# UBT.net
KiCad netlist of a schematic drawn in Altium Designer
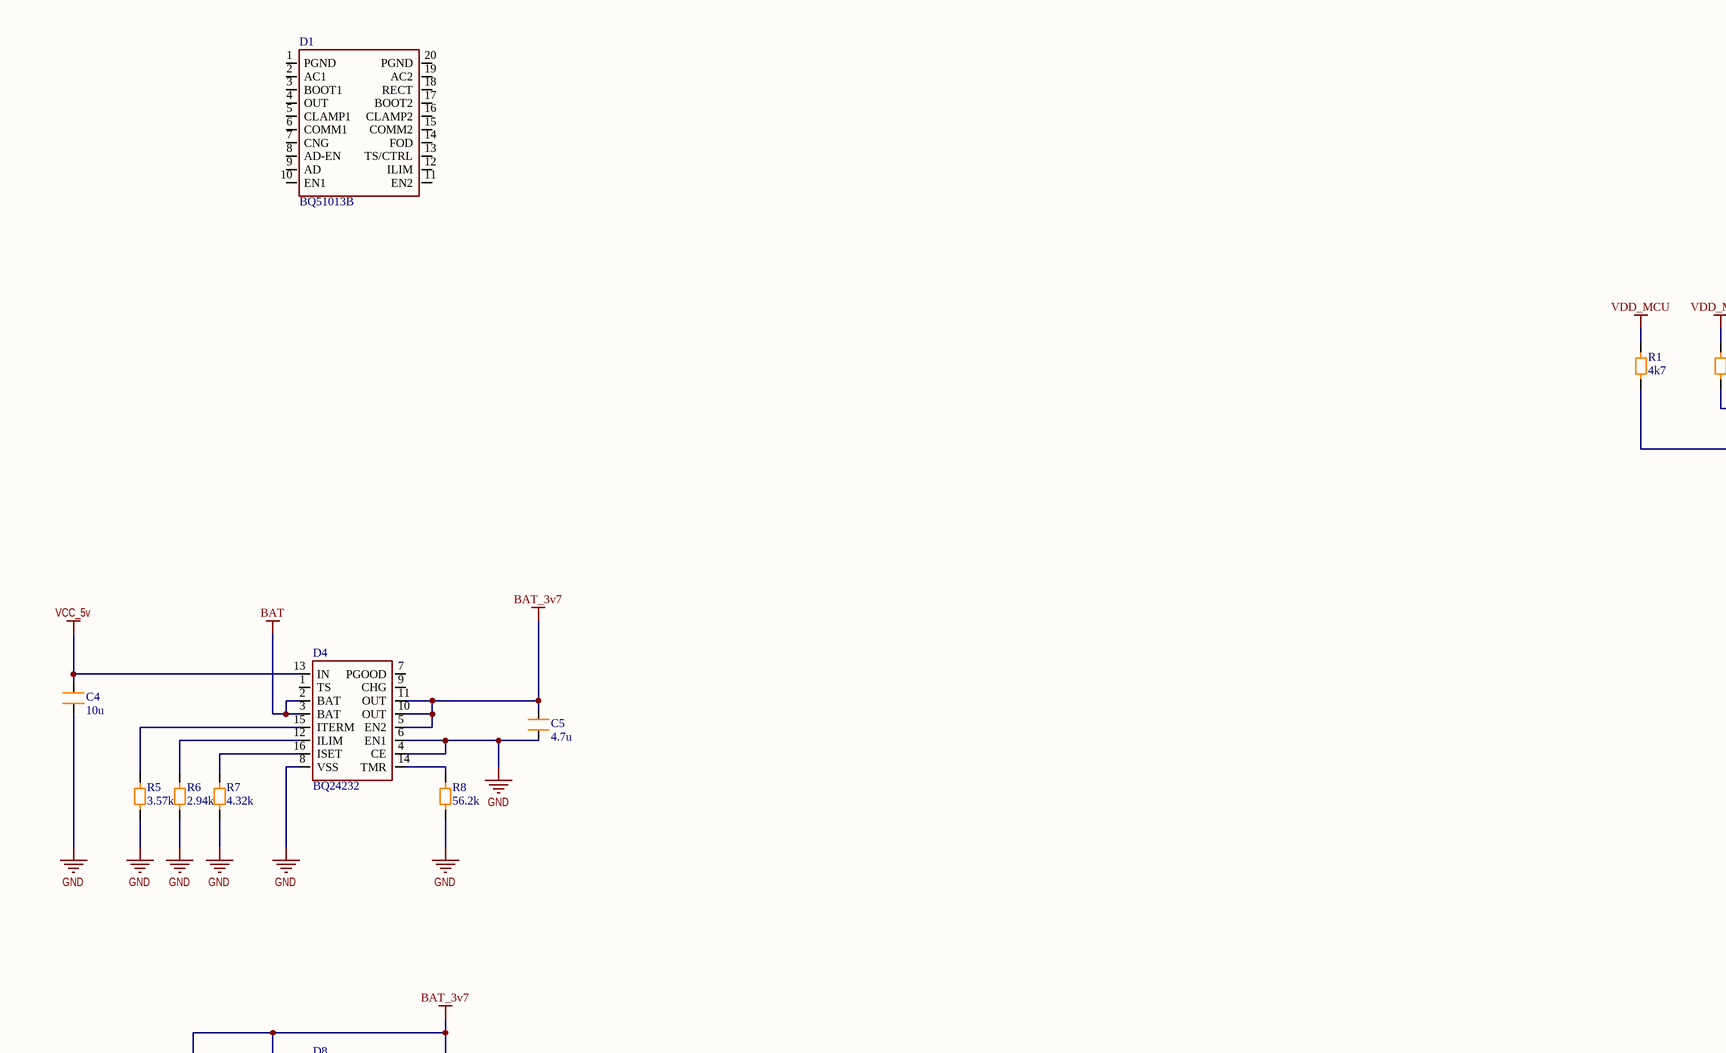
[diagram p0: UBT.SchDoc, top left]
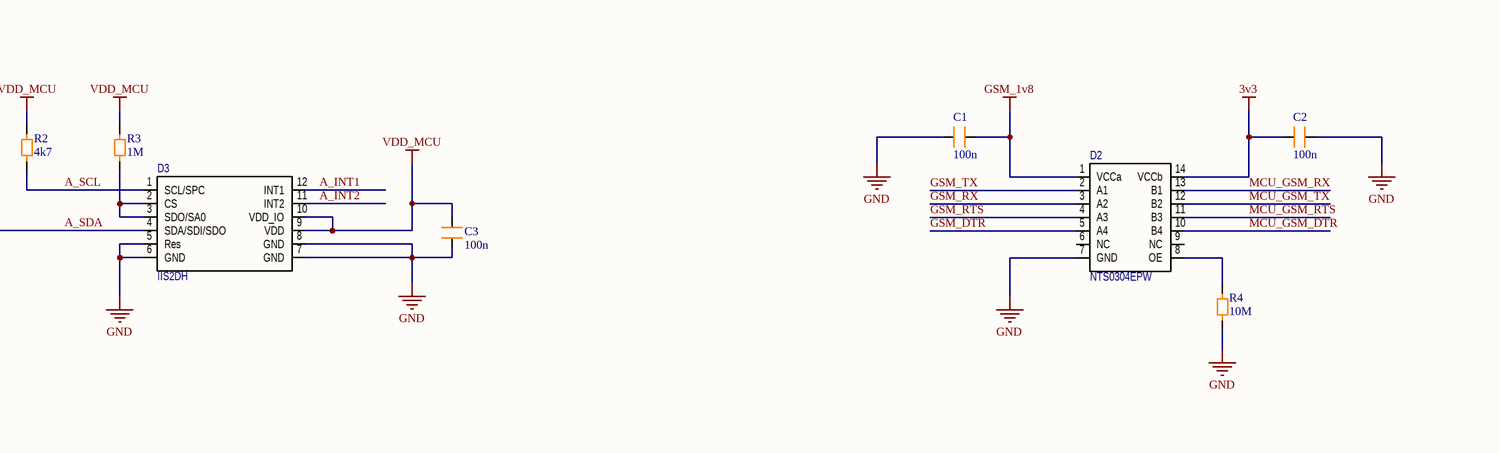
[diagram p1: UBT.SchDoc, top right]
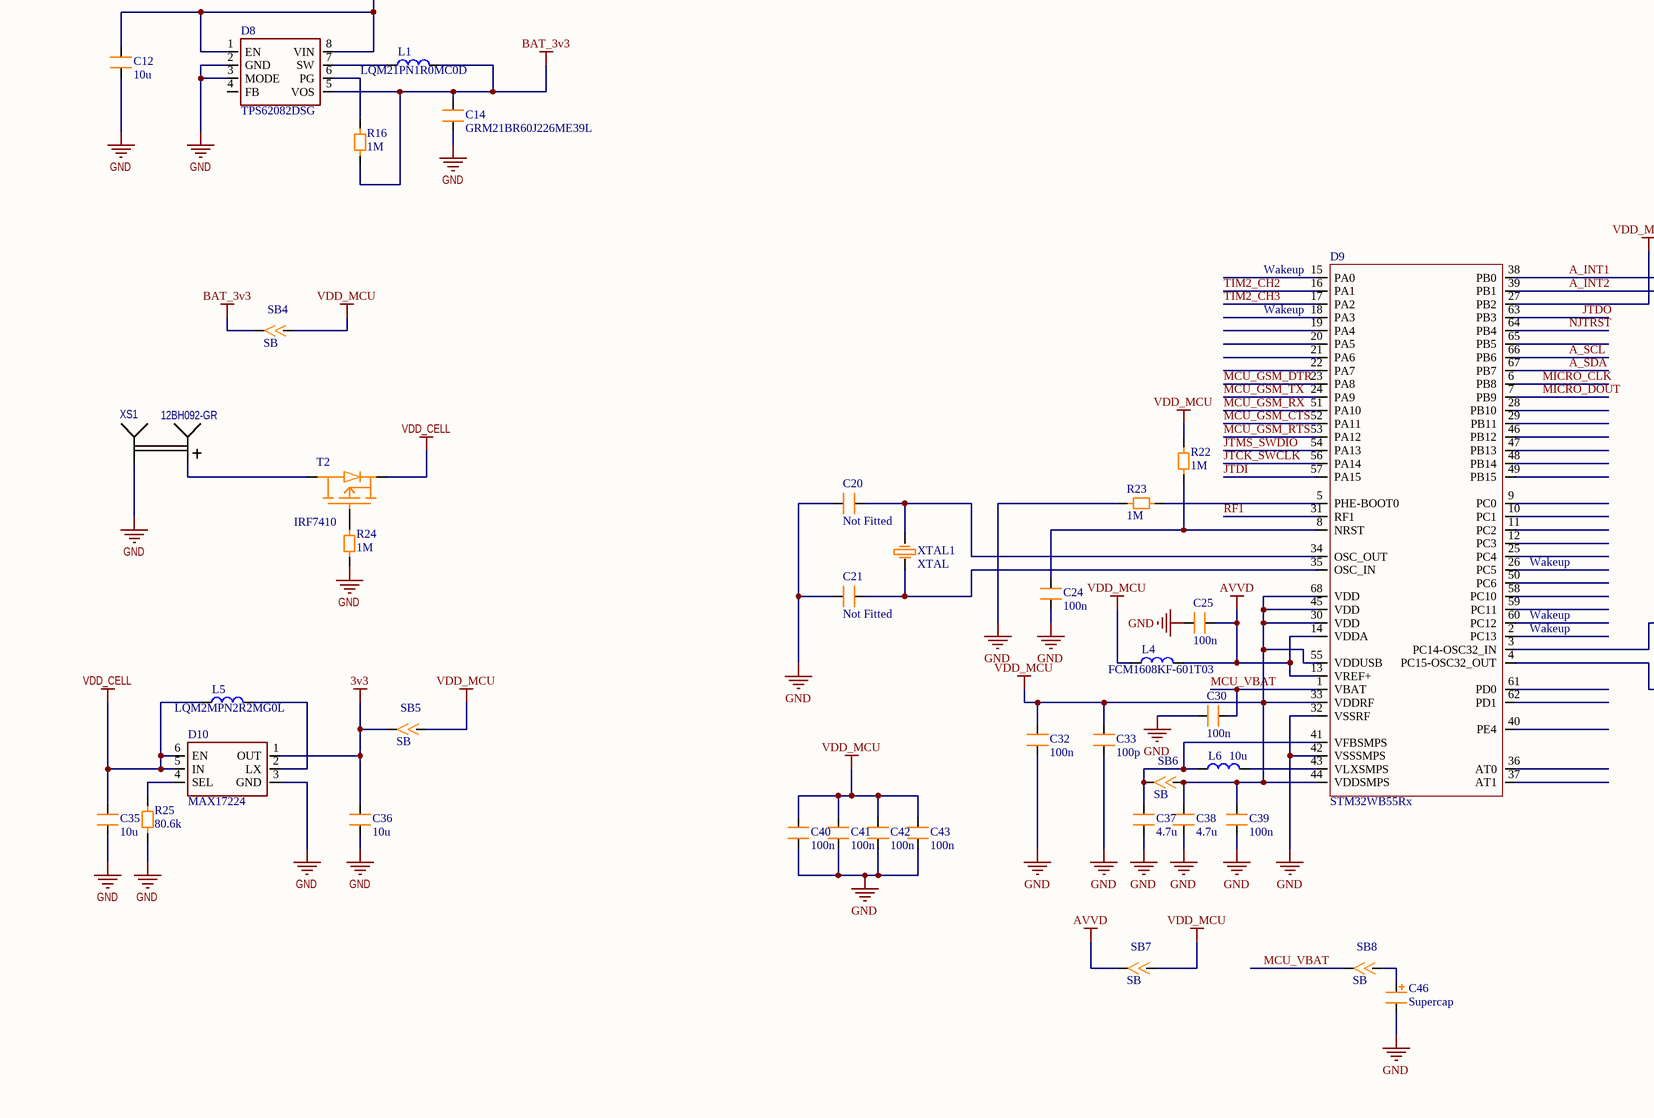
[diagram p2: UBT.SchDoc, bottom left]
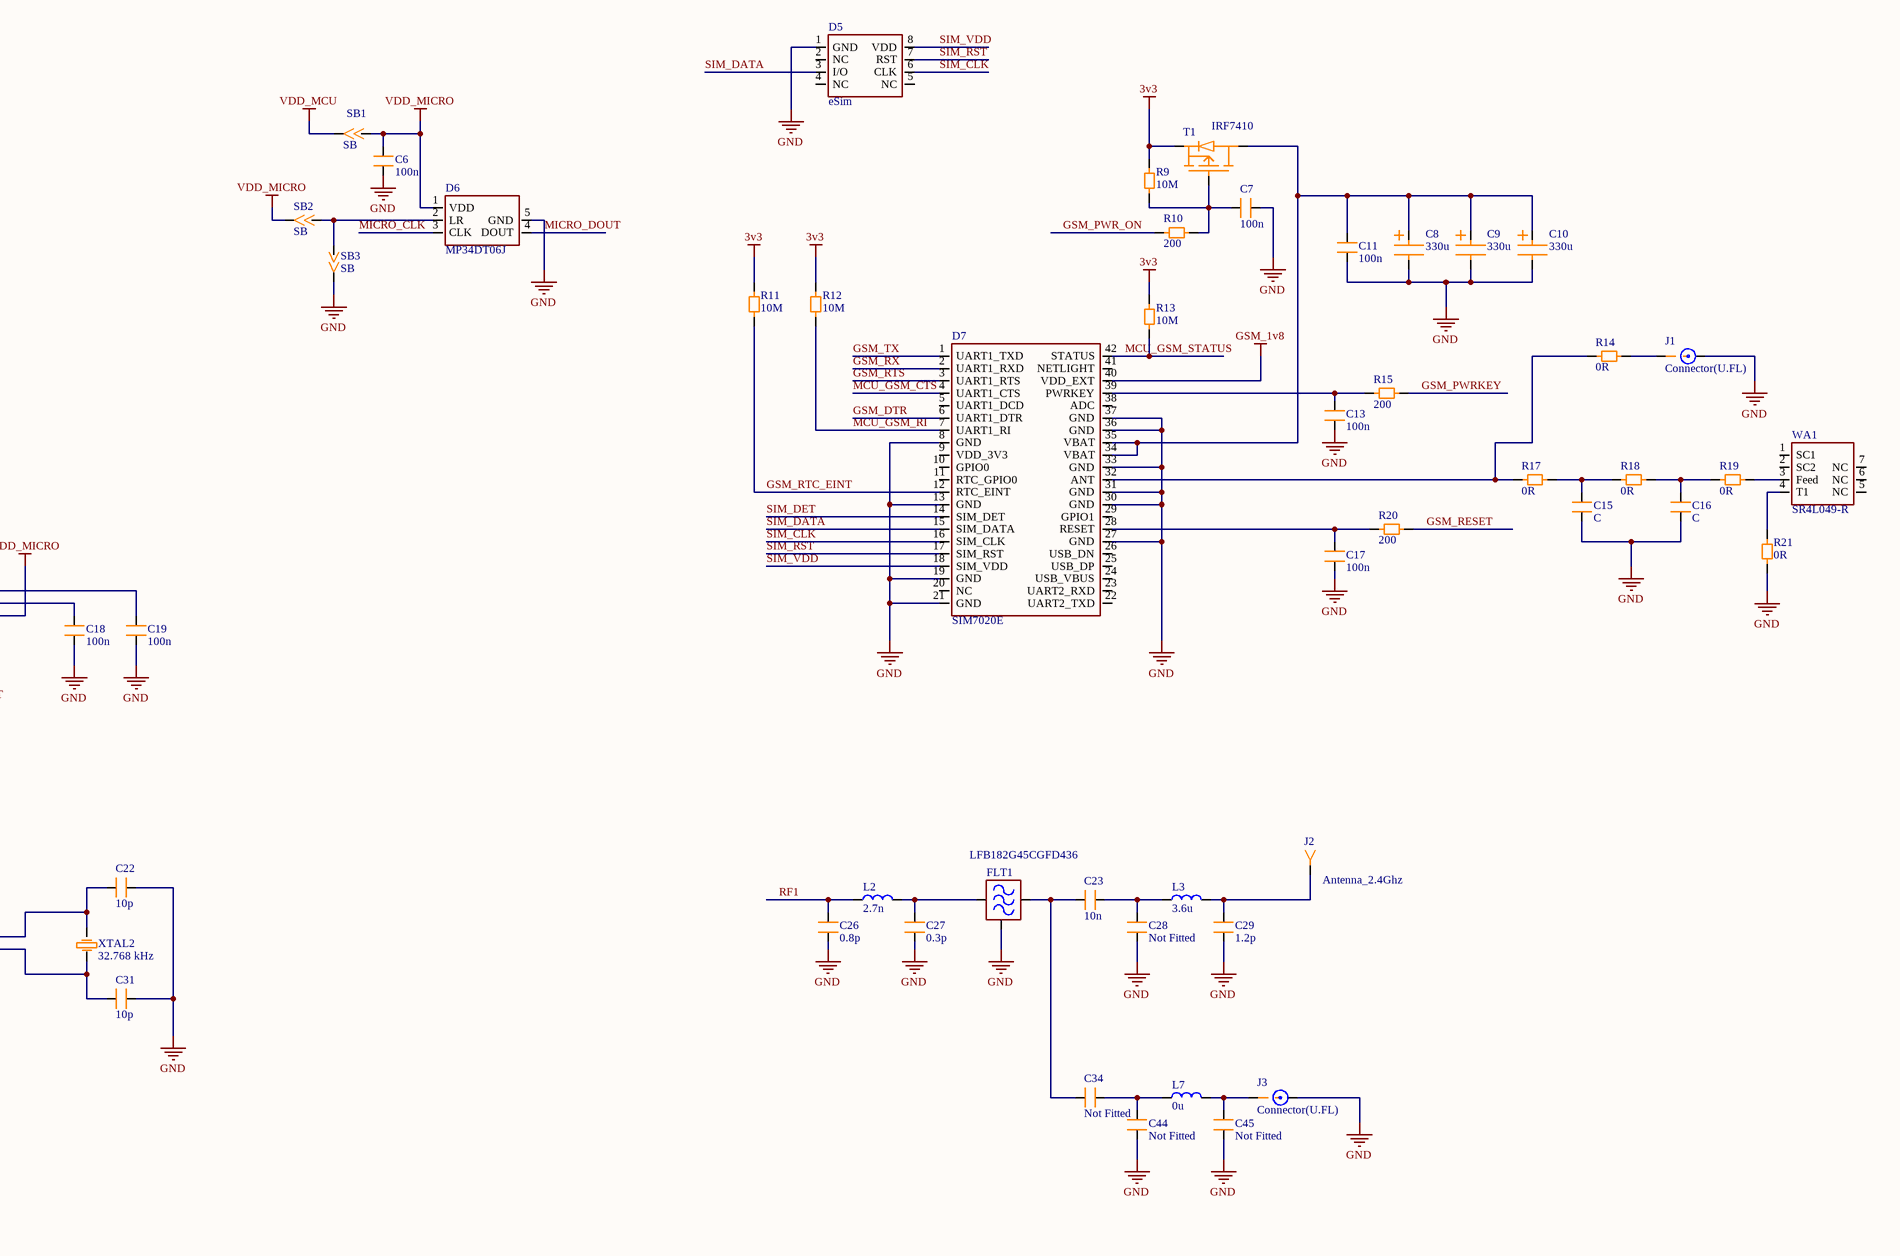
[diagram p3: UBT.SchDoc, bottom right]

(export (version "E")
  (design (tool "Eeschema 10.0.6"))
  (components
    (comp (ref "C1") (value "100n") (footprint "C0402") (libsource (lib "Schlib1") (part "C")))
    (comp (ref "C2") (value "100n") (footprint "C0402") (libsource (lib "Schlib1") (part "C")))
    (comp (ref "C3") (value "100n") (footprint "C0402") (libsource (lib "Schlib1") (part "C")))
    (comp (ref "C4") (value "10u") (footprint "C0603") (libsource (lib "Schlib1") (part "C")))
    (comp (ref "C5") (value "4.7u") (footprint "C0603") (libsource (lib "Schlib1") (part "C")))
    (comp (ref "C6") (value "100n") (footprint "C0402") (libsource (lib "Schlib1") (part "C")))
    (comp (ref "C7") (value "100n") (footprint "C0402") (libsource (lib "Schlib1") (part "C")))
    (comp (ref "C8") (value "330u") (footprint "C_TYPE_D") (libsource (lib "Schlib1") (part "C_TANTAL")))
    (comp (ref "C9") (value "330u") (footprint "C_TYPE_D") (libsource (lib "Schlib1") (part "C_TANTAL")))
    (comp (ref "C10") (value "330u") (footprint "C_TYPE_D") (libsource (lib "Schlib1") (part "C_TANTAL")))
    (comp (ref "C11") (value "100n") (footprint "C0402") (libsource (lib "Schlib1") (part "C")))
    (comp (ref "C12") (value "10u") (footprint "C0603") (libsource (lib "Schlib1") (part "C")))
    (comp (ref "C13") (value "100n") (footprint "C0402") (libsource (lib "Schlib1") (part "C")))
    (comp (ref "C14") (value "GRM21BR60J226ME39L") (footprint "C0805") (libsource (lib "Schlib1") (part "C")))
    (comp (ref "C15") (value "C") (footprint "C0402") (libsource (lib "Schlib1") (part "C")))
    (comp (ref "C16") (value "C") (footprint "C0402") (libsource (lib "Schlib1") (part "C")))
    (comp (ref "C17") (value "100n") (footprint "C0402") (libsource (lib "Schlib1") (part "C")))
    (comp (ref "C18") (value "100n") (footprint "C0402") (libsource (lib "Schlib1") (part "C")))
    (comp (ref "C19") (value "100n") (footprint "C0402") (libsource (lib "Schlib1") (part "C")))
    (comp (ref "C20") (value "Not Fitted") (footprint "C0402") (libsource (lib "Schlib1") (part "C")))
    (comp (ref "C21") (value "Not Fitted") (footprint "C0402") (libsource (lib "Schlib1") (part "C")))
    (comp (ref "C22") (value "10p") (footprint "C0402") (libsource (lib "Schlib1") (part "C")))
    (comp (ref "C23") (value "10n") (footprint "C0402") (libsource (lib "Schlib1") (part "C")))
    (comp (ref "C24") (value "100n") (footprint "C0402") (libsource (lib "Schlib1") (part "C")))
    (comp (ref "C25") (value "100n") (footprint "C0402") (libsource (lib "Schlib1") (part "C")))
    (comp (ref "C26") (value "0.8p") (footprint "C0402") (libsource (lib "Schlib1") (part "C")))
    (comp (ref "C27") (value "0.3p") (footprint "C0402") (libsource (lib "Schlib1") (part "C")))
    (comp (ref "C28") (value "Not Fitted") (footprint "C0402") (libsource (lib "Schlib1") (part "C")))
    (comp (ref "C29") (value "1.2p") (footprint "C0402") (libsource (lib "Schlib1") (part "C")))
    (comp (ref "C30") (value "100n") (footprint "C0402") (libsource (lib "Schlib1") (part "C")))
    (comp (ref "C31") (value "10p") (footprint "C0402") (libsource (lib "Schlib1") (part "C")))
    (comp (ref "C32") (value "100n") (footprint "C0402") (libsource (lib "Schlib1") (part "C")))
    (comp (ref "C33") (value "100p") (footprint "C0402") (libsource (lib "Schlib1") (part "C")))
    (comp (ref "C34") (value "Not Fitted") (footprint "C0402") (libsource (lib "Schlib1") (part "C")))
    (comp (ref "C35") (value "10u") (footprint "C0603") (libsource (lib "Schlib1") (part "C")))
    (comp (ref "C36") (value "10u") (footprint "C0603") (libsource (lib "Schlib1") (part "C")))
    (comp (ref "C37") (value "4.7u") (footprint "C0402") (libsource (lib "Schlib1") (part "C")))
    (comp (ref "C38") (value "4.7u") (footprint "C0402") (libsource (lib "Schlib1") (part "C")))
    (comp (ref "C39") (value "100n") (footprint "C0402") (libsource (lib "Schlib1") (part "C")))
    (comp (ref "C40") (value "100n") (footprint "C0402") (libsource (lib "Schlib1") (part "C")))
    (comp (ref "C41") (value "100n") (footprint "C0402") (libsource (lib "Schlib1") (part "C")))
    (comp (ref "C42") (value "100n") (footprint "C0402") (libsource (lib "Schlib1") (part "C")))
    (comp (ref "C43") (value "100n") (footprint "C0402") (libsource (lib "Schlib1") (part "C")))
    (comp (ref "C44") (value "Not Fitted") (footprint "C0402") (libsource (lib "Schlib1") (part "C")))
    (comp (ref "C45") (value "Not Fitted") (footprint "C0402") (libsource (lib "Schlib1") (part "C")))
    (comp (ref "C46")
      (value "Supercap")
      (footprint "Supercap_5mm")
      (libsource (lib "Schlib1") (part "Supercap"))
    )
    (comp (ref "D1") (value "BQ51013B") (footprint "VQFN20") (libsource (lib "Schlib1") (part "BQ51013B")))
    (comp (ref "D2")
      (value "NTS0304EPW")
      (footprint "TSSOP14")
      (libsource (lib "Schlib1") (part "NTS0304EPW"))
    )
    (comp (ref "D3") (value "IIS2DH") (footprint "LGA12") (libsource (lib "Schlib1") (part "IIS2DH")))
    (comp (ref "D4") (value "BQ24232") (footprint "VQFN-16") (libsource (lib "Schlib1") (part "BQ24232")))
    (comp (ref "D5") (value "eSim") (footprint "VQFN8") (libsource (lib "Schlib1") (part "eSim")))
    (comp (ref "D6")
      (value "MP34DT06J")
      (footprint "MP34DT06J")
      (libsource (lib "Schlib1") (part "MP34DT06J"))
    )
    (comp (ref "D7") (value "SIM7020E") (footprint "SIM7020E") (libsource (lib "Schlib1") (part "SIM7020E")))
    (comp (ref "D8") (value "TPS62082DSG") (footprint "WSON8") (libsource (lib "Schlib1") (part "TPS62081")))
    (comp (ref "D9")
      (value "STM32WB55Rx")
      (footprint "VFQFPN68")
      (libsource (lib "Schlib1") (part "STM32WB55Rx"))
    )
    (comp (ref "D10") (value "MAX17224") (libsource (lib "Schlib1") (part "MAX17224")))
    (comp (ref "FLT1")
      (value "LFB182G45CGFD436")
      (footprint "LFB182G45CGFD436")
      (libsource (lib "Schlib1") (part "LFB182G45CGFD436"))
    )
    (comp (ref "J1")
      (value "Connector(U.FL)")
      (footprint "U.FL")
      (libsource (lib "Schlib1") (part "Connector(U.FL)"))
    )
    (comp (ref "J2")
      (value "Antenna_2.4Ghz")
      (footprint "Antenna_2.4Ghz")
      (libsource (lib "Schlib1") (part "Antenna_2.4Ghz"))
    )
    (comp (ref "J3")
      (value "Connector(U.FL)")
      (footprint "U.FL")
      (libsource (lib "Schlib1") (part "Connector(U.FL)"))
    )
    (comp (ref "L1") (value "LQM21PN1R0MC0D") (footprint "L0805") (libsource (lib "Schlib1") (part "L")))
    (comp (ref "L2") (value "2.7n") (footprint "L0402") (libsource (lib "Schlib1") (part "L")))
    (comp (ref "L3") (value "3.6u") (footprint "L0402") (libsource (lib "Schlib1") (part "L")))
    (comp (ref "L4") (value "FCM1608KF-601T03") (footprint "L1608") (libsource (lib "Schlib1") (part "L")))
    (comp (ref "L5") (value "LQM2MPN2R2MG0L") (footprint "L2016") (libsource (lib "Schlib1") (part "L")))
    (comp (ref "L6") (value "10u") (footprint "L0805") (libsource (lib "Schlib1") (part "L")))
    (comp (ref "L7") (value "0u") (footprint "L0402") (libsource (lib "Schlib1") (part "L")))
    (comp (ref "R1") (value "4k7") (footprint "R0402") (libsource (lib "Schlib1") (part "R")))
    (comp (ref "R2") (value "4k7") (footprint "R0402") (libsource (lib "Schlib1") (part "R")))
    (comp (ref "R3") (value "1M") (footprint "R0402") (libsource (lib "Schlib1") (part "R")))
    (comp (ref "R4") (value "10M") (footprint "R0402") (libsource (lib "Schlib1") (part "R")))
    (comp (ref "R5") (value "3.57k") (footprint "R0402") (libsource (lib "Schlib1") (part "R")))
    (comp (ref "R6") (value "2.94k") (footprint "R0402") (libsource (lib "Schlib1") (part "R")))
    (comp (ref "R7") (value "4.32k") (footprint "R0402") (libsource (lib "Schlib1") (part "R")))
    (comp (ref "R8") (value "56.2k") (footprint "R0402") (libsource (lib "Schlib1") (part "R")))
    (comp (ref "R9") (value "10M") (footprint "R0402") (libsource (lib "Schlib1") (part "R")))
    (comp (ref "R10") (value "200") (footprint "R0402") (libsource (lib "Schlib1") (part "R")))
    (comp (ref "R11") (value "10M") (footprint "R0402") (libsource (lib "Schlib1") (part "R")))
    (comp (ref "R12") (value "10M") (footprint "R0402") (libsource (lib "Schlib1") (part "R")))
    (comp (ref "R13") (value "10M") (footprint "R0402") (libsource (lib "Schlib1") (part "R")))
    (comp (ref "R14") (value "0R") (footprint "R0402") (libsource (lib "Schlib1") (part "R")))
    (comp (ref "R15") (value "200") (footprint "R0402") (libsource (lib "Schlib1") (part "R")))
    (comp (ref "R16") (value "1M") (footprint "R0402") (libsource (lib "Schlib1") (part "R")))
    (comp (ref "R17") (value "0R") (footprint "R0402") (libsource (lib "Schlib1") (part "R")))
    (comp (ref "R18") (value "0R") (footprint "R0402") (libsource (lib "Schlib1") (part "R")))
    (comp (ref "R19") (value "0R") (footprint "R0402") (libsource (lib "Schlib1") (part "R")))
    (comp (ref "R20") (value "200") (footprint "R0402") (libsource (lib "Schlib1") (part "R")))
    (comp (ref "R21") (value "0R") (footprint "R0402") (libsource (lib "Schlib1") (part "R")))
    (comp (ref "R22") (value "1M") (footprint "R0402") (libsource (lib "Schlib1") (part "R")))
    (comp (ref "R23") (value "1M") (footprint "R0402") (libsource (lib "Schlib1") (part "R")))
    (comp (ref "R24") (value "1M") (footprint "R0402") (libsource (lib "Schlib1") (part "R")))
    (comp (ref "R25") (value "80.6k") (footprint "R0402") (libsource (lib "Schlib1") (part "R")))
    (comp (ref "SB1") (value "SB") (footprint "SB") (libsource (lib "Schlib1") (part "SB")))
    (comp (ref "SB2") (value "SB") (footprint "SB") (libsource (lib "Schlib1") (part "SB")))
    (comp (ref "SB3") (value "SB") (footprint "SB") (libsource (lib "Schlib1") (part "SB")))
    (comp (ref "SB4") (value "SB") (footprint "SB") (libsource (lib "Schlib1") (part "SB")))
    (comp (ref "SB5") (value "SB") (footprint "SB") (libsource (lib "Schlib1") (part "SB")))
    (comp (ref "SB6") (value "SB") (footprint "SB") (libsource (lib "Schlib1") (part "SB")))
    (comp (ref "SB7") (value "SB") (footprint "SB") (libsource (lib "Schlib1") (part "SB")))
    (comp (ref "SB8") (value "SB") (footprint "SB") (libsource (lib "Schlib1") (part "SB")))
    (comp (ref "T1") (value "IRF7410") (footprint "SO8") (libsource (lib "Schlib1") (part "IRF7410")))
    (comp (ref "T2") (value "IRF7410") (footprint "SO8") (libsource (lib "Schlib1") (part "IRF7410")))
    (comp (ref "WA1")
      (value "SR4L049-R")
      (footprint "SR4L049-R")
      (libsource (lib "Schlib1") (part "SR4L049-R"))
    )
    (comp (ref "XS1")
      (value "12BH092-GR")
      (footprint "12BH092-GR")
      (libsource (lib "Schlib1") (part "12BH092-GR"))
    )
    (comp (ref "XTAL1") (value "XTAL") (footprint "NX2016SA") (libsource (lib "Schlib1") (part "XTAL")))
    (comp (ref "XTAL2")
      (value "32.768 kHz")
      (footprint "NX2012SA")
      (libsource (lib "Schlib1") (part "32.768 kHz"))
    )
  )
  (nets
    (net (code "1") (name "/A_INT1") (class "Default")
      (node (ref "C19") (pin "2") (pinfunction "2_2") (pintype "passive"))
      (node (ref "D3") (pin "12") (pinfunction "INT1_12") (pintype "passive"))
      (node (ref "D9") (pin "38") (pinfunction "PB0_38") (pintype "passive"))
    )
    (net (code "2") (name "/A_INT2") (class "Default")
      (node (ref "C18") (pin "2") (pinfunction "2_2") (pintype "passive"))
      (node (ref "D3") (pin "11") (pinfunction "INT2_11") (pintype "passive"))
      (node (ref "D9") (pin "39") (pinfunction "PB1_39") (pintype "passive"))
    )
    (net (code "3") (name "/A_SCL") (class "Default")
      (node (ref "D3") (pin "1") (pinfunction "SCL/SPC_1") (pintype "passive"))
      (node (ref "D9") (pin "66") (pinfunction "PB6_66") (pintype "passive"))
      (node (ref "R2") (pin "1") (pinfunction "1_1") (pintype "passive"))
    )
    (net (code "4") (name "/A_SDA") (class "Default")
      (node (ref "D3") (pin "4") (pinfunction "SDA/SDI/SDO_4") (pintype "passive"))
      (node (ref "D9") (pin "67") (pinfunction "PB7_67") (pintype "passive"))
      (node (ref "R1") (pin "1") (pinfunction "1_1") (pintype "passive"))
    )
    (net (code "5") (name "/GSM_DTR") (class "Default")
      (node (ref "D2") (pin "5") (pinfunction "A4_5") (pintype "passive"))
      (node (ref "D7") (pin "6") (pinfunction "UART1_DTR_6") (pintype "passive"))
    )
    (net (code "6") (name "/GSM_PWRKEY") (class "Default")
      (node (ref "R15") (pin "2") (pinfunction "2_2") (pintype "passive"))
    )
    (net (code "7") (name "/GSM_PWR_ON") (class "Default")
      (node (ref "R10") (pin "1") (pinfunction "1_1") (pintype "passive"))
    )
    (net (code "8") (name "/GSM_RESET") (class "Default")
      (node (ref "R20") (pin "2") (pinfunction "2_2") (pintype "passive"))
    )
    (net (code "9") (name "/GSM_RTC_EINT") (class "Default")
      (node (ref "D7") (pin "12") (pinfunction "RTC_EINT_12") (pintype "passive"))
      (node (ref "R11") (pin "2") (pinfunction "2_2") (pintype "passive"))
    )
    (net (code "10") (name "/GSM_RTS") (class "Default")
      (node (ref "D2") (pin "4") (pinfunction "A3_4") (pintype "passive"))
      (node (ref "D7") (pin "3") (pinfunction "UART1_RTS_3") (pintype "passive"))
    )
    (net (code "11") (name "/GSM_RX") (class "Default")
      (node (ref "D2") (pin "3") (pinfunction "A2_3") (pintype "passive"))
      (node (ref "D7") (pin "2") (pinfunction "UART1_RXD_2") (pintype "passive"))
    )
    (net (code "12") (name "/GSM_TX") (class "Default")
      (node (ref "D2") (pin "2") (pinfunction "A1_2") (pintype "passive"))
      (node (ref "D7") (pin "1") (pinfunction "UART1_TXD_1") (pintype "passive"))
    )
    (net (code "13") (name "/JTCK_SWCLK") (class "Default")
      (node (ref "D9") (pin "56") (pinfunction "PA14_56") (pintype "passive"))
    )
    (net (code "14") (name "/JTDI") (class "Default")
      (node (ref "D9") (pin "57") (pinfunction "PA15_57") (pintype "passive"))
    )
    (net (code "15") (name "/JTDO") (class "Default")
      (node (ref "D9") (pin "63") (pinfunction "PB3_63") (pintype "passive"))
    )
    (net (code "16") (name "/JTMS_SWDIO") (class "Default")
      (node (ref "D9") (pin "54") (pinfunction "PA13_54") (pintype "passive"))
    )
    (net (code "17") (name "/MCU_GSM_CTS") (class "Default")
      (node (ref "D7") (pin "4") (pinfunction "UART1_CTS_4") (pintype "passive"))
      (node (ref "D9") (pin "52") (pinfunction "PA11_52") (pintype "passive"))
    )
    (net (code "18") (name "/MCU_GSM_DTR") (class "Default")
      (node (ref "D2") (pin "10") (pinfunction "B4_10") (pintype "passive"))
      (node (ref "D9") (pin "23") (pinfunction "PA8_23") (pintype "passive"))
    )
    (net (code "19") (name "/MCU_GSM_RI") (class "Default")
      (node (ref "D7") (pin "7") (pinfunction "UART1_RI_7") (pintype "passive"))
      (node (ref "R12") (pin "2") (pinfunction "2_2") (pintype "passive"))
    )
    (net (code "20") (name "/MCU_GSM_RTS") (class "Default")
      (node (ref "D2") (pin "11") (pinfunction "B3_11") (pintype "passive"))
      (node (ref "D9") (pin "53") (pinfunction "PA12_53") (pintype "passive"))
    )
    (net (code "21") (name "/MCU_GSM_RX") (class "Default")
      (node (ref "D2") (pin "13") (pinfunction "B1_13") (pintype "passive"))
      (node (ref "D9") (pin "51") (pinfunction "PA10_51") (pintype "passive"))
    )
    (net (code "22") (name "/MCU_GSM_STATUS") (class "Default")
      (node (ref "D7") (pin "42") (pinfunction "STATUS_42") (pintype "passive"))
      (node (ref "R13") (pin "2") (pinfunction "2_2") (pintype "passive"))
    )
    (net (code "23") (name "/MCU_GSM_TX") (class "Default")
      (node (ref "D2") (pin "12") (pinfunction "B2_12") (pintype "passive"))
      (node (ref "D9") (pin "24") (pinfunction "PA9_24") (pintype "passive"))
    )
    (net (code "24") (name "/MCU_VBAT") (class "Default")
      (node (ref "C30") (pin "1") (pinfunction "1_1") (pintype "passive"))
      (node (ref "D9") (pin "1") (pinfunction "VBAT_1") (pintype "passive"))
      (node (ref "SB8") (pin "1") (pinfunction "1_1") (pintype "passive"))
    )
    (net (code "25") (name "/MICRO_CLK") (class "Default")
      (node (ref "D6") (pin "3") (pinfunction "CLK_3") (pintype "passive"))
      (node (ref "D9") (pin "6") (pinfunction "PB8_6") (pintype "passive"))
    )
    (net (code "26") (name "/NJTRST") (class "Default")
      (node (ref "D9") (pin "64") (pinfunction "PB4_64") (pintype "passive"))
    )
    (net (code "27") (name "/RF1") (class "Default")
      (node (ref "C26") (pin "2") (pinfunction "2_2") (pintype "passive"))
      (node (ref "D9") (pin "31") (pinfunction "RF1_31") (pintype "passive"))
      (node (ref "L2") (pin "1") (pinfunction "1_1") (pintype "passive"))
    )
    (net (code "28") (name "/SIM_CLK") (class "Default")
      (node (ref "D5") (pin "6") (pinfunction "CLK_6") (pintype "passive"))
      (node (ref "D7") (pin "16") (pinfunction "SIM_CLK_16") (pintype "passive"))
    )
    (net (code "29") (name "/SIM_DATA") (class "Default")
      (node (ref "D5") (pin "3") (pinfunction "I/O_3") (pintype "passive"))
      (node (ref "D7") (pin "15") (pinfunction "SIM_DATA_15") (pintype "passive"))
    )
    (net (code "30") (name "/SIM_DET") (class "Default")
      (node (ref "D7") (pin "14") (pinfunction "SIM_DET_14") (pintype "passive"))
    )
    (net (code "31") (name "/SIM_RST") (class "Default")
      (node (ref "D5") (pin "7") (pinfunction "RST_7") (pintype "passive"))
      (node (ref "D7") (pin "17") (pinfunction "SIM_RST_17") (pintype "passive"))
    )
    (net (code "32") (name "/SIM_VDD") (class "Default")
      (node (ref "D5") (pin "8") (pinfunction "VDD_8") (pintype "passive"))
      (node (ref "D7") (pin "18") (pinfunction "SIM_VDD_18") (pintype "passive"))
    )
    (net (code "33") (name "/TIM2_CH2") (class "Default")
      (node (ref "D9") (pin "16") (pinfunction "PA1_16") (pintype "passive"))
    )
    (net (code "34") (name "/TIM2_CH3") (class "Default")
      (node (ref "D9") (pin "17") (pinfunction "PA2_17") (pintype "passive"))
    )
    (net (code "35") (name "3v3") (class "Default")
      (node (ref "C2") (pin "1") (pinfunction "1_1") (pintype "passive"))
      (node (ref "C36") (pin "2") (pinfunction "2_2") (pintype "passive"))
      (node (ref "D10") (pin "1") (pinfunction "OUT_1") (pintype "passive"))
      (node (ref "D2") (pin "14") (pinfunction "VCCb_14") (pintype "passive"))
      (node (ref "R11") (pin "1") (pinfunction "1_1") (pintype "passive"))
      (node (ref "R12") (pin "1") (pinfunction "1_1") (pintype "passive"))
      (node (ref "R13") (pin "1") (pinfunction "1_1") (pintype "passive"))
      (node (ref "R9") (pin "1") (pinfunction "1_1") (pintype "passive"))
      (node (ref "SB5") (pin "1") (pinfunction "1_1") (pintype "passive"))
      (node (ref "T1") (pin "1") (pinfunction "1_1") (pintype "passive"))
    )
    (net (code "36") (name "AVVD") (class "Default")
      (node (ref "C25") (pin "1") (pinfunction "1_1") (pintype "passive"))
      (node (ref "D9") (pin "13") (pinfunction "VREF+_13") (pintype "passive"))
      (node (ref "D9") (pin "14") (pinfunction "VDDA_14") (pintype "passive"))
      (node (ref "L4") (pin "2") (pinfunction "2_2") (pintype "passive"))
      (node (ref "SB7") (pin "1") (pinfunction "1_1") (pintype "passive"))
    )
    (net (code "37") (name "BAT") (class "Default")
      (node (ref "D4") (pin "2") (pinfunction "BAT_2") (pintype "passive"))
      (node (ref "D4") (pin "3") (pinfunction "BAT_3") (pintype "passive"))
    )
    (net (code "38") (name "BAT_3v3") (class "Default")
      (node (ref "C14") (pin "2") (pinfunction "2_2") (pintype "passive"))
      (node (ref "D8") (pin "5") (pinfunction "VOS_5") (pintype "passive"))
      (node (ref "L1") (pin "2") (pinfunction "2_2") (pintype "passive"))
      (node (ref "R16") (pin "1") (pinfunction "1_1") (pintype "passive"))
      (node (ref "SB4") (pin "1") (pinfunction "1_1") (pintype "passive"))
    )
    (net (code "39") (name "BAT_3v7") (class "Default")
      (node (ref "C12") (pin "2") (pinfunction "2_2") (pintype "passive"))
      (node (ref "C5") (pin "2") (pinfunction "2_2") (pintype "passive"))
      (node (ref "D4") (pin "10") (pinfunction "OUT_10") (pintype "passive"))
      (node (ref "D4") (pin "11") (pinfunction "OUT_11") (pintype "passive"))
      (node (ref "D4") (pin "5") (pinfunction "EN2_5") (pintype "passive"))
      (node (ref "D8") (pin "1") (pinfunction "EN_1") (pintype "passive"))
      (node (ref "D8") (pin "8") (pinfunction "VIN_8") (pintype "passive"))
    )
    (net (code "40") (name "GND") (class "Default")
      (node (ref "C1") (pin "1") (pinfunction "1_1") (pintype "passive"))
      (node (ref "C10") (pin "2") (pinfunction "2_2") (pintype "passive"))
      (node (ref "C11") (pin "1") (pinfunction "1_1") (pintype "passive"))
      (node (ref "C12") (pin "1") (pinfunction "1_1") (pintype "passive"))
      (node (ref "C13") (pin "1") (pinfunction "1_1") (pintype "passive"))
      (node (ref "C14") (pin "1") (pinfunction "1_1") (pintype "passive"))
      (node (ref "C15") (pin "1") (pinfunction "1_1") (pintype "passive"))
      (node (ref "C16") (pin "1") (pinfunction "1_1") (pintype "passive"))
      (node (ref "C17") (pin "1") (pinfunction "1_1") (pintype "passive"))
      (node (ref "C18") (pin "1") (pinfunction "1_1") (pintype "passive"))
      (node (ref "C19") (pin "1") (pinfunction "1_1") (pintype "passive"))
      (node (ref "C2") (pin "2") (pinfunction "2_2") (pintype "passive"))
      (node (ref "C20") (pin "2") (pinfunction "2_2") (pintype "passive"))
      (node (ref "C21") (pin "2") (pinfunction "2_2") (pintype "passive"))
      (node (ref "C22") (pin "2") (pinfunction "2_2") (pintype "passive"))
      (node (ref "C24") (pin "1") (pinfunction "1_1") (pintype "passive"))
      (node (ref "C25") (pin "2") (pinfunction "2_2") (pintype "passive"))
      (node (ref "C26") (pin "1") (pinfunction "1_1") (pintype "passive"))
      (node (ref "C27") (pin "1") (pinfunction "1_1") (pintype "passive"))
      (node (ref "C28") (pin "1") (pinfunction "1_1") (pintype "passive"))
      (node (ref "C29") (pin "1") (pinfunction "1_1") (pintype "passive"))
      (node (ref "C3") (pin "1") (pinfunction "1_1") (pintype "passive"))
      (node (ref "C30") (pin "2") (pinfunction "2_2") (pintype "passive"))
      (node (ref "C31") (pin "2") (pinfunction "2_2") (pintype "passive"))
      (node (ref "C32") (pin "1") (pinfunction "1_1") (pintype "passive"))
      (node (ref "C33") (pin "1") (pinfunction "1_1") (pintype "passive"))
      (node (ref "C35") (pin "1") (pinfunction "1_1") (pintype "passive"))
      (node (ref "C36") (pin "1") (pinfunction "1_1") (pintype "passive"))
      (node (ref "C37") (pin "1") (pinfunction "1_1") (pintype "passive"))
      (node (ref "C38") (pin "1") (pinfunction "1_1") (pintype "passive"))
      (node (ref "C39") (pin "1") (pinfunction "1_1") (pintype "passive"))
      (node (ref "C4") (pin "1") (pinfunction "1_1") (pintype "passive"))
      (node (ref "C40") (pin "1") (pinfunction "1_1") (pintype "passive"))
      (node (ref "C41") (pin "1") (pinfunction "1_1") (pintype "passive"))
      (node (ref "C42") (pin "1") (pinfunction "1_1") (pintype "passive"))
      (node (ref "C43") (pin "1") (pinfunction "1_1") (pintype "passive"))
      (node (ref "C44") (pin "1") (pinfunction "1_1") (pintype "passive"))
      (node (ref "C45") (pin "1") (pinfunction "1_1") (pintype "passive"))
      (node (ref "C46") (pin "2") (pinfunction "2_2") (pintype "passive"))
      (node (ref "C5") (pin "1") (pinfunction "1_1") (pintype "passive"))
      (node (ref "C6") (pin "1") (pinfunction "1_1") (pintype "passive"))
      (node (ref "C7") (pin "1") (pinfunction "1_1") (pintype "passive"))
      (node (ref "C8") (pin "2") (pinfunction "2_2") (pintype "passive"))
      (node (ref "C9") (pin "2") (pinfunction "2_2") (pintype "passive"))
      (node (ref "D10") (pin "3") (pinfunction "GND_3") (pintype "passive"))
      (node (ref "D2") (pin "7") (pinfunction "GND_7") (pintype "passive"))
      (node (ref "D3") (pin "5") (pinfunction "Res_5") (pintype "passive"))
      (node (ref "D3") (pin "6") (pinfunction "GND_6") (pintype "passive"))
      (node (ref "D3") (pin "7") (pinfunction "GND_7") (pintype "passive"))
      (node (ref "D3") (pin "8") (pinfunction "GND_8") (pintype "passive"))
      (node (ref "D4") (pin "4") (pinfunction "CE_4") (pintype "passive"))
      (node (ref "D4") (pin "6") (pinfunction "EN1_6") (pintype "passive"))
      (node (ref "D4") (pin "8") (pinfunction "VSS_8") (pintype "passive"))
      (node (ref "D5") (pin "1") (pinfunction "GND_1") (pintype "passive"))
      (node (ref "D6") (pin "4") (pinfunction "DOUT_4") (pintype "passive"))
      (node (ref "D6") (pin "5") (pinfunction "GND_5") (pintype "passive"))
      (node (ref "D7") (pin "13") (pinfunction "GND_13") (pintype "passive"))
      (node (ref "D7") (pin "19") (pinfunction "GND_19") (pintype "passive"))
      (node (ref "D7") (pin "21") (pinfunction "GND_21") (pintype "passive"))
      (node (ref "D7") (pin "27") (pinfunction "GND_27") (pintype "passive"))
      (node (ref "D7") (pin "30") (pinfunction "GND_30") (pintype "passive"))
      (node (ref "D7") (pin "31") (pinfunction "GND_31") (pintype "passive"))
      (node (ref "D7") (pin "33") (pinfunction "GND_33") (pintype "passive"))
      (node (ref "D7") (pin "36") (pinfunction "GND_36") (pintype "passive"))
      (node (ref "D7") (pin "37") (pinfunction "GND_37") (pintype "passive"))
      (node (ref "D7") (pin "8") (pinfunction "GND_8") (pintype "passive"))
      (node (ref "D8") (pin "2") (pinfunction "GND_2") (pintype "passive"))
      (node (ref "D8") (pin "3") (pinfunction "MODE_3") (pintype "passive"))
      (node (ref "D9") (pin "32") (pinfunction "VSSRF_32") (pintype "passive"))
      (node (ref "D9") (pin "42") (pinfunction "VSSSMPS_42") (pintype "passive"))
      (node (ref "D9") (pin "7") (pinfunction "PB9_7") (pintype "passive"))
      (node (ref "FLT1") (pin "2") (pinfunction "2_2") (pintype "passive"))
      (node (ref "J1") (pin "2") (pinfunction "2_2") (pintype "passive"))
      (node (ref "J3") (pin "2") (pinfunction "2_2") (pintype "passive"))
      (node (ref "R21") (pin "1") (pinfunction "1_1") (pintype "passive"))
      (node (ref "R23") (pin "2") (pinfunction "2_2") (pintype "passive"))
      (node (ref "R24") (pin "1") (pinfunction "1_1") (pintype "passive"))
      (node (ref "R25") (pin "1") (pinfunction "1_1") (pintype "passive"))
      (node (ref "R4") (pin "2") (pinfunction "2_2") (pintype "passive"))
      (node (ref "R5") (pin "1") (pinfunction "1_1") (pintype "passive"))
      (node (ref "R6") (pin "1") (pinfunction "1_1") (pintype "passive"))
      (node (ref "R7") (pin "1") (pinfunction "1_1") (pintype "passive"))
      (node (ref "R8") (pin "1") (pinfunction "1_1") (pintype "passive"))
      (node (ref "SB3") (pin "1") (pinfunction "1_1") (pintype "passive"))
      (node (ref "XS1") (pin "2") (pinfunction "2_2") (pintype "passive"))
    )
    (net (code "41") (name "GSM_1v8") (class "Default")
      (node (ref "C1") (pin "2") (pinfunction "2_2") (pintype "passive"))
      (node (ref "D2") (pin "1") (pinfunction "VCCa_1") (pintype "passive"))
      (node (ref "D7") (pin "40") (pinfunction "VDD_EXT_40") (pintype "passive"))
    )
    (net (code "42") (name "Net-(C7-Pad2)") (class "Default")
      (node (ref "C7") (pin "2") (pinfunction "2_2") (pintype "passive"))
      (node (ref "R10") (pin "2") (pinfunction "2_2") (pintype "passive"))
      (node (ref "R9") (pin "2") (pinfunction "2_2") (pintype "passive"))
      (node (ref "T1") (pin "4") (pinfunction "4_4") (pintype "passive"))
    )
    (net (code "43") (name "Net-(C10-Pad1)") (class "Default")
      (node (ref "C10") (pin "1") (pinfunction "1_1") (pintype "passive"))
      (node (ref "C11") (pin "2") (pinfunction "2_2") (pintype "passive"))
      (node (ref "C8") (pin "1") (pinfunction "1_1") (pintype "passive"))
      (node (ref "C9") (pin "1") (pinfunction "1_1") (pintype "passive"))
      (node (ref "D7") (pin "34") (pinfunction "VBAT_34") (pintype "passive"))
      (node (ref "D7") (pin "35") (pinfunction "VBAT_35") (pintype "passive"))
      (node (ref "T1") (pin "5") (pinfunction "5_5") (pintype "passive"))
    )
    (net (code "44") (name "Net-(C15-Pad2)") (class "Default")
      (node (ref "C15") (pin "2") (pinfunction "2_2") (pintype "passive"))
      (node (ref "R17") (pin "2") (pinfunction "2_2") (pintype "passive"))
      (node (ref "R18") (pin "1") (pinfunction "1_1") (pintype "passive"))
    )
    (net (code "45") (name "Net-(C16-Pad2)") (class "Default")
      (node (ref "C16") (pin "2") (pinfunction "2_2") (pintype "passive"))
      (node (ref "R18") (pin "2") (pinfunction "2_2") (pintype "passive"))
      (node (ref "R19") (pin "1") (pinfunction "1_1") (pintype "passive"))
    )
    (net (code "46") (name "Net-(C23-Pad1)") (class "Default")
      (node (ref "C23") (pin "1") (pinfunction "1_1") (pintype "passive"))
      (node (ref "C34") (pin "1") (pinfunction "1_1") (pintype "passive"))
      (node (ref "FLT1") (pin "3") (pinfunction "3_3") (pintype "passive"))
    )
    (net (code "47") (name "Net-(C23-Pad2)") (class "Default")
      (node (ref "C23") (pin "2") (pinfunction "2_2") (pintype "passive"))
      (node (ref "C28") (pin "2") (pinfunction "2_2") (pintype "passive"))
      (node (ref "L3") (pin "1") (pinfunction "1_1") (pintype "passive"))
    )
    (net (code "48") (name "Net-(C27-Pad2)") (class "Default")
      (node (ref "C27") (pin "2") (pinfunction "2_2") (pintype "passive"))
      (node (ref "FLT1") (pin "1") (pinfunction "1_1") (pintype "passive"))
      (node (ref "L2") (pin "2") (pinfunction "2_2") (pintype "passive"))
    )
    (net (code "49") (name "Net-(C29-Pad2)") (class "Default")
      (node (ref "C29") (pin "2") (pinfunction "2_2") (pintype "passive"))
      (node (ref "J2") (pin "1") (pinfunction "1_1") (pintype "passive"))
      (node (ref "L3") (pin "2") (pinfunction "2_2") (pintype "passive"))
    )
    (net (code "50") (name "Net-(C34-Pad2)") (class "Default")
      (node (ref "C34") (pin "2") (pinfunction "2_2") (pintype "passive"))
      (node (ref "C44") (pin "2") (pinfunction "2_2") (pintype "passive"))
      (node (ref "L7") (pin "1") (pinfunction "1_1") (pintype "passive"))
    )
    (net (code "51") (name "Net-(C45-Pad2)") (class "Default")
      (node (ref "C45") (pin "2") (pinfunction "2_2") (pintype "passive"))
      (node (ref "J3") (pin "1") (pinfunction "1_1") (pintype "passive"))
      (node (ref "L7") (pin "2") (pinfunction "2_2") (pintype "passive"))
    )
    (net (code "52") (name "Net-(C46-Pad1)") (class "Default")
      (node (ref "C46") (pin "1") (pinfunction "1_1") (pintype "passive"))
      (node (ref "SB8") (pin "2") (pinfunction "2_2") (pintype "passive"))
    )
    (net (code "53") (name "Net-(D2-OE)") (class "Default")
      (node (ref "D2") (pin "8") (pinfunction "OE_8") (pintype "passive"))
      (node (ref "R4") (pin "1") (pinfunction "1_1") (pintype "passive"))
    )
    (net (code "54") (name "Net-(D3-CS)") (class "Default")
      (node (ref "D3") (pin "2") (pinfunction "CS_2") (pintype "passive"))
      (node (ref "D3") (pin "3") (pinfunction "SDO/SA0_3") (pintype "passive"))
      (node (ref "R3") (pin "1") (pinfunction "1_1") (pintype "passive"))
    )
    (net (code "55") (name "Net-(D4-ILIM)") (class "Default")
      (node (ref "D4") (pin "12") (pinfunction "ILIM_12") (pintype "passive"))
      (node (ref "R6") (pin "2") (pinfunction "2_2") (pintype "passive"))
    )
    (net (code "56") (name "Net-(D4-ISET)") (class "Default")
      (node (ref "D4") (pin "16") (pinfunction "ISET_16") (pintype "passive"))
      (node (ref "R7") (pin "2") (pinfunction "2_2") (pintype "passive"))
    )
    (net (code "57") (name "Net-(D4-ITERM)") (class "Default")
      (node (ref "D4") (pin "15") (pinfunction "ITERM_15") (pintype "passive"))
      (node (ref "R5") (pin "2") (pinfunction "2_2") (pintype "passive"))
    )
    (net (code "58") (name "Net-(D4-TMR)") (class "Default")
      (node (ref "D4") (pin "14") (pinfunction "TMR_14") (pintype "passive"))
      (node (ref "R8") (pin "2") (pinfunction "2_2") (pintype "passive"))
    )
    (net (code "59") (name "Net-(D6-LR)") (class "Default")
      (node (ref "D6") (pin "2") (pinfunction "LR_2") (pintype "passive"))
      (node (ref "SB2") (pin "2") (pinfunction "2_2") (pintype "passive"))
      (node (ref "SB3") (pin "2") (pinfunction "2_2") (pintype "passive"))
    )
    (net (code "60") (name "Net-(D7-ANT)") (class "Default")
      (node (ref "D7") (pin "32") (pinfunction "ANT_32") (pintype "passive"))
      (node (ref "R14") (pin "1") (pinfunction "1_1") (pintype "passive"))
      (node (ref "R17") (pin "1") (pinfunction "1_1") (pintype "passive"))
    )
    (net (code "61") (name "Net-(D7-PWRKEY)") (class "Default")
      (node (ref "C13") (pin "2") (pinfunction "2_2") (pintype "passive"))
      (node (ref "D7") (pin "39") (pinfunction "PWRKEY_39") (pintype "passive"))
      (node (ref "R15") (pin "1") (pinfunction "1_1") (pintype "passive"))
    )
    (net (code "62") (name "Net-(D7-RESET)") (class "Default")
      (node (ref "C17") (pin "2") (pinfunction "2_2") (pintype "passive"))
      (node (ref "D7") (pin "28") (pinfunction "RESET_28") (pintype "passive"))
      (node (ref "R20") (pin "1") (pinfunction "1_1") (pintype "passive"))
    )
    (net (code "63") (name "Net-(D8-PG)") (class "Default")
      (node (ref "D8") (pin "6") (pinfunction "PG_6") (pintype "passive"))
      (node (ref "R16") (pin "2") (pinfunction "2_2") (pintype "passive"))
    )
    (net (code "64") (name "Net-(D8-SW)") (class "Default")
      (node (ref "D8") (pin "7") (pinfunction "SW_7") (pintype "passive"))
      (node (ref "L1") (pin "1") (pinfunction "1_1") (pintype "passive"))
    )
    (net (code "65") (name "Net-(D9-NRST)") (class "Default")
      (node (ref "C24") (pin "2") (pinfunction "2_2") (pintype "passive"))
      (node (ref "D9") (pin "8") (pinfunction "NRST_8") (pintype "passive"))
      (node (ref "R22") (pin "1") (pinfunction "1_1") (pintype "passive"))
    )
    (net (code "66") (name "Net-(D9-OSC_IN)") (class "Default")
      (node (ref "C21") (pin "1") (pinfunction "1_1") (pintype "passive"))
      (node (ref "D9") (pin "35") (pinfunction "OSC_IN_35") (pintype "passive"))
      (node (ref "XTAL1") (pin "1") (pinfunction "1_1") (pintype "passive"))
    )
    (net (code "67") (name "Net-(D9-OSC_OUT)") (class "Default")
      (node (ref "C20") (pin "1") (pinfunction "1_1") (pintype "passive"))
      (node (ref "D9") (pin "34") (pinfunction "OSC_OUT_34") (pintype "passive"))
      (node (ref "XTAL1") (pin "2") (pinfunction "2_2") (pintype "passive"))
    )
    (net (code "68") (name "Net-(D9-PC14-OSC32_IN)") (class "Default")
      (node (ref "C22") (pin "1") (pinfunction "1_1") (pintype "passive"))
      (node (ref "D9") (pin "3") (pinfunction "PC14-OSC32_IN_3") (pintype "passive"))
      (node (ref "XTAL2") (pin "2") (pinfunction "2_2") (pintype "passive"))
    )
    (net (code "69") (name "Net-(D9-PC15-OSC32_OUT)") (class "Default")
      (node (ref "C31") (pin "1") (pinfunction "1_1") (pintype "passive"))
      (node (ref "D9") (pin "4") (pinfunction "PC15-OSC32_OUT_4") (pintype "passive"))
      (node (ref "XTAL2") (pin "1") (pinfunction "1_1") (pintype "passive"))
    )
    (net (code "70") (name "Net-(D9-PHE-BOOT0)") (class "Default")
      (node (ref "D9") (pin "5") (pinfunction "PHE-BOOT0_5") (pintype "passive"))
      (node (ref "R23") (pin "1") (pinfunction "1_1") (pintype "passive"))
    )
    (net (code "71") (name "Net-(D9-VFBSMPS)") (class "Default")
      (node (ref "C37") (pin "2") (pinfunction "2_2") (pintype "passive"))
      (node (ref "D9") (pin "41") (pinfunction "VFBSMPS_41") (pintype "passive"))
      (node (ref "L6") (pin "1") (pinfunction "1_1") (pintype "passive"))
      (node (ref "SB6") (pin "1") (pinfunction "1_1") (pintype "passive"))
    )
    (net (code "72") (name "Net-(D9-VLXSMPS)") (class "Default")
      (node (ref "D9") (pin "43") (pinfunction "VLXSMPS_43") (pintype "passive"))
      (node (ref "L6") (pin "2") (pinfunction "2_2") (pintype "passive"))
    )
    (net (code "73") (name "Net-(D10-LX)") (class "Default")
      (node (ref "D10") (pin "2") (pinfunction "LX_2") (pintype "passive"))
      (node (ref "L5") (pin "2") (pinfunction "2_2") (pintype "passive"))
    )
    (net (code "74") (name "Net-(D10-SEL)") (class "Default")
      (node (ref "D10") (pin "4") (pinfunction "SEL_4") (pintype "passive"))
      (node (ref "R25") (pin "2") (pinfunction "2_2") (pintype "passive"))
    )
    (net (code "75") (name "Net-(J1-Pad1)") (class "Default")
      (node (ref "J1") (pin "1") (pinfunction "1_1") (pintype "passive"))
      (node (ref "R14") (pin "2") (pinfunction "2_2") (pintype "passive"))
    )
    (net (code "76") (name "Net-(R24-Pad2)") (class "Default")
      (node (ref "R24") (pin "2") (pinfunction "2_2") (pintype "passive"))
      (node (ref "T2") (pin "4") (pinfunction "4_4") (pintype "passive"))
    )
    (net (code "77") (name "Net-(T2-Pad5)") (class "Default")
      (node (ref "T2") (pin "5") (pinfunction "5_5") (pintype "passive"))
      (node (ref "XS1") (pin "1") (pinfunction "1_1") (pintype "passive"))
    )
    (net (code "78") (name "Net-(WA1-Feed)") (class "Default")
      (node (ref "R19") (pin "2") (pinfunction "2_2") (pintype "passive"))
      (node (ref "WA1") (pin "3") (pinfunction "Feed_3") (pintype "passive"))
    )
    (net (code "79") (name "Net-(WA1-T1)") (class "Default")
      (node (ref "R21") (pin "2") (pinfunction "2_2") (pintype "passive"))
      (node (ref "WA1") (pin "4") (pinfunction "T1_4") (pintype "passive"))
    )
    (net (code "80") (name "VCC_5v") (class "Default")
      (node (ref "C4") (pin "2") (pinfunction "2_2") (pintype "passive"))
      (node (ref "D4") (pin "13") (pinfunction "IN_13") (pintype "passive"))
    )
    (net (code "81") (name "VDD_CELL") (class "Default")
      (node (ref "C35") (pin "2") (pinfunction "2_2") (pintype "passive"))
      (node (ref "D10") (pin "5") (pinfunction "IN_5") (pintype "passive"))
      (node (ref "D10") (pin "6") (pinfunction "EN_6") (pintype "passive"))
      (node (ref "L5") (pin "1") (pinfunction "1_1") (pintype "passive"))
      (node (ref "T2") (pin "1") (pinfunction "1_1") (pintype "passive"))
    )
    (net (code "82") (name "VDD_MCU") (class "Default")
      (node (ref "C3") (pin "2") (pinfunction "2_2") (pintype "passive"))
      (node (ref "C32") (pin "2") (pinfunction "2_2") (pintype "passive"))
      (node (ref "C33") (pin "2") (pinfunction "2_2") (pintype "passive"))
      (node (ref "C38") (pin "2") (pinfunction "2_2") (pintype "passive"))
      (node (ref "C39") (pin "2") (pinfunction "2_2") (pintype "passive"))
      (node (ref "C40") (pin "2") (pinfunction "2_2") (pintype "passive"))
      (node (ref "C41") (pin "2") (pinfunction "2_2") (pintype "passive"))
      (node (ref "C42") (pin "2") (pinfunction "2_2") (pintype "passive"))
      (node (ref "C43") (pin "2") (pinfunction "2_2") (pintype "passive"))
      (node (ref "D3") (pin "10") (pinfunction "VDD_IO_10") (pintype "passive"))
      (node (ref "D3") (pin "9") (pinfunction "VDD_9") (pintype "passive"))
      (node (ref "D9") (pin "30") (pinfunction "VDD_30") (pintype "passive"))
      (node (ref "D9") (pin "33") (pinfunction "VDDRF_33") (pintype "passive"))
      (node (ref "D9") (pin "44") (pinfunction "VDDSMPS_44") (pintype "passive"))
      (node (ref "D9") (pin "45") (pinfunction "VDD_45") (pintype "passive"))
      (node (ref "D9") (pin "55") (pinfunction "VDDUSB_55") (pintype "passive"))
      (node (ref "D9") (pin "68") (pinfunction "VDD_68") (pintype "passive"))
      (node (ref "L4") (pin "1") (pinfunction "1_1") (pintype "passive"))
      (node (ref "R1") (pin "2") (pinfunction "2_2") (pintype "passive"))
      (node (ref "R2") (pin "2") (pinfunction "2_2") (pintype "passive"))
      (node (ref "R22") (pin "2") (pinfunction "2_2") (pintype "passive"))
      (node (ref "R3") (pin "2") (pinfunction "2_2") (pintype "passive"))
      (node (ref "SB1") (pin "1") (pinfunction "1_1") (pintype "passive"))
      (node (ref "SB4") (pin "2") (pinfunction "2_2") (pintype "passive"))
      (node (ref "SB5") (pin "2") (pinfunction "2_2") (pintype "passive"))
      (node (ref "SB6") (pin "2") (pinfunction "2_2") (pintype "passive"))
      (node (ref "SB7") (pin "2") (pinfunction "2_2") (pintype "passive"))
    )
    (net (code "83") (name "VDD_MICRO") (class "Default")
      (node (ref "C6") (pin "2") (pinfunction "2_2") (pintype "passive"))
      (node (ref "D6") (pin "1") (pinfunction "VDD_1") (pintype "passive"))
      (node (ref "D9") (pin "27") (pinfunction "PB2_27") (pintype "passive"))
      (node (ref "SB1") (pin "2") (pinfunction "2_2") (pintype "passive"))
      (node (ref "SB2") (pin "1") (pinfunction "1_1") (pintype "passive"))
    )
    (net (code "84") (name "unconnected-(D1-AC1-Pad2)") (class "Default")
      (node (ref "D1") (pin "2") (pinfunction "AC1_2") (pintype "passive"))
    )
    (net (code "85") (name "unconnected-(D1-AC2-Pad19)") (class "Default")
      (node (ref "D1") (pin "19") (pinfunction "AC2_19") (pintype "passive"))
    )
    (net (code "86") (name "unconnected-(D1-AD-EN-Pad8)") (class "Default")
      (node (ref "D1") (pin "8") (pinfunction "AD-EN_8") (pintype "passive"))
    )
    (net (code "87") (name "unconnected-(D1-AD-Pad9)") (class "Default")
      (node (ref "D1") (pin "9") (pinfunction "AD_9") (pintype "passive"))
    )
    (net (code "88") (name "unconnected-(D1-BOOT1-Pad3)") (class "Default")
      (node (ref "D1") (pin "3") (pinfunction "BOOT1_3") (pintype "passive"))
    )
    (net (code "89") (name "unconnected-(D1-BOOT2-Pad17)") (class "Default")
      (node (ref "D1") (pin "17") (pinfunction "BOOT2_17") (pintype "passive"))
    )
    (net (code "90") (name "unconnected-(D1-CLAMP1-Pad5)") (class "Default")
      (node (ref "D1") (pin "5") (pinfunction "CLAMP1_5") (pintype "passive"))
    )
    (net (code "91") (name "unconnected-(D1-CLAMP2-Pad16)") (class "Default")
      (node (ref "D1") (pin "16") (pinfunction "CLAMP2_16") (pintype "passive"))
    )
    (net (code "92") (name "unconnected-(D1-CNG-Pad7)") (class "Default")
      (node (ref "D1") (pin "7") (pinfunction "CNG_7") (pintype "passive"))
    )
    (net (code "93") (name "unconnected-(D1-COMM1-Pad6)") (class "Default")
      (node (ref "D1") (pin "6") (pinfunction "COMM1_6") (pintype "passive"))
    )
    (net (code "94") (name "unconnected-(D1-COMM2-Pad15)") (class "Default")
      (node (ref "D1") (pin "15") (pinfunction "COMM2_15") (pintype "passive"))
    )
    (net (code "95") (name "unconnected-(D1-EN1-Pad10)") (class "Default")
      (node (ref "D1") (pin "10") (pinfunction "EN1_10") (pintype "passive"))
    )
    (net (code "96") (name "unconnected-(D1-EN2-Pad11)") (class "Default")
      (node (ref "D1") (pin "11") (pinfunction "EN2_11") (pintype "passive"))
    )
    (net (code "97") (name "unconnected-(D1-FOD-Pad14)") (class "Default")
      (node (ref "D1") (pin "14") (pinfunction "FOD_14") (pintype "passive"))
    )
    (net (code "98") (name "unconnected-(D1-ILIM-Pad12)") (class "Default")
      (node (ref "D1") (pin "12") (pinfunction "ILIM_12") (pintype "passive"))
    )
    (net (code "99") (name "unconnected-(D1-OUT-Pad4)") (class "Default")
      (node (ref "D1") (pin "4") (pinfunction "OUT_4") (pintype "passive"))
    )
    (net (code "100") (name "unconnected-(D1-PGND-Pad1)") (class "Default")
      (node (ref "D1") (pin "1") (pinfunction "PGND_1") (pintype "passive"))
    )
    (net (code "101") (name "unconnected-(D1-PGND-Pad20)") (class "Default")
      (node (ref "D1") (pin "20") (pinfunction "PGND_20") (pintype "passive"))
    )
    (net (code "102") (name "unconnected-(D1-RECT-Pad18)") (class "Default")
      (node (ref "D1") (pin "18") (pinfunction "RECT_18") (pintype "passive"))
    )
    (net (code "103") (name "unconnected-(D1-TS{slash}CTRL-Pad13)") (class "Default")
      (node (ref "D1") (pin "13") (pinfunction "TS/CTRL_13") (pintype "passive"))
    )
    (net (code "104") (name "unconnected-(D2-NC-Pad6)") (class "Default")
      (node (ref "D2") (pin "6") (pinfunction "NC_6") (pintype "passive"))
    )
    (net (code "105") (name "unconnected-(D2-NC-Pad9)") (class "Default")
      (node (ref "D2") (pin "9") (pinfunction "NC_9") (pintype "passive"))
    )
    (net (code "106") (name "unconnected-(D4-CHG-Pad9)") (class "Default")
      (node (ref "D4") (pin "9") (pinfunction "CHG_9") (pintype "passive"))
    )
    (net (code "107") (name "unconnected-(D4-PGOOD-Pad7)") (class "Default")
      (node (ref "D4") (pin "7") (pinfunction "PGOOD_7") (pintype "passive"))
    )
    (net (code "108") (name "unconnected-(D4-TS-Pad1)") (class "Default")
      (node (ref "D4") (pin "1") (pinfunction "TS_1") (pintype "passive"))
    )
    (net (code "109") (name "unconnected-(D5-NC-Pad2)") (class "Default")
      (node (ref "D5") (pin "2") (pinfunction "NC_2") (pintype "passive"))
    )
    (net (code "110") (name "unconnected-(D5-NC-Pad4)") (class "Default")
      (node (ref "D5") (pin "4") (pinfunction "NC_4") (pintype "passive"))
    )
    (net (code "111") (name "unconnected-(D5-NC-Pad5)") (class "Default")
      (node (ref "D5") (pin "5") (pinfunction "NC_5") (pintype "passive"))
    )
    (net (code "112") (name "unconnected-(D7-ADC-Pad38)") (class "Default")
      (node (ref "D7") (pin "38") (pinfunction "ADC_38") (pintype "passive"))
    )
    (net (code "113") (name "unconnected-(D7-GPIO0-Pad10)") (class "Default")
      (node (ref "D7") (pin "10") (pinfunction "GPIO0_10") (pintype "passive"))
    )
    (net (code "114") (name "unconnected-(D7-GPIO1-Pad29)") (class "Default")
      (node (ref "D7") (pin "29") (pinfunction "GPIO1_29") (pintype "passive"))
    )
    (net (code "115") (name "unconnected-(D7-NC-Pad20)") (class "Default")
      (node (ref "D7") (pin "20") (pinfunction "NC_20") (pintype "passive"))
    )
    (net (code "116") (name "unconnected-(D7-NETLIGHT-Pad41)") (class "Default")
      (node (ref "D7") (pin "41") (pinfunction "NETLIGHT_41") (pintype "passive"))
    )
    (net (code "117") (name "unconnected-(D7-RTC_GPIO0-Pad11)") (class "Default")
      (node (ref "D7") (pin "11") (pinfunction "RTC_GPIO0_11") (pintype "passive"))
    )
    (net (code "118") (name "unconnected-(D7-UART1_DCD-Pad5)") (class "Default")
      (node (ref "D7") (pin "5") (pinfunction "UART1_DCD_5") (pintype "passive"))
    )
    (net (code "119") (name "unconnected-(D7-UART2_RXD-Pad23)") (class "Default")
      (node (ref "D7") (pin "23") (pinfunction "UART2_RXD_23") (pintype "passive"))
    )
    (net (code "120") (name "unconnected-(D7-UART2_TXD-Pad22)") (class "Default")
      (node (ref "D7") (pin "22") (pinfunction "UART2_TXD_22") (pintype "passive"))
    )
    (net (code "121") (name "unconnected-(D7-USB_DN-Pad26)") (class "Default")
      (node (ref "D7") (pin "26") (pinfunction "USB_DN_26") (pintype "passive"))
    )
    (net (code "122") (name "unconnected-(D7-USB_DP-Pad25)") (class "Default")
      (node (ref "D7") (pin "25") (pinfunction "USB_DP_25") (pintype "passive"))
    )
    (net (code "123") (name "unconnected-(D7-USB_VBUS-Pad24)") (class "Default")
      (node (ref "D7") (pin "24") (pinfunction "USB_VBUS_24") (pintype "passive"))
    )
    (net (code "124") (name "unconnected-(D7-VDD_3V3-Pad9)") (class "Default")
      (node (ref "D7") (pin "9") (pinfunction "VDD_3V3_9") (pintype "passive"))
    )
    (net (code "125") (name "unconnected-(D8-FB-Pad4)") (class "Default")
      (node (ref "D8") (pin "4") (pinfunction "FB_4") (pintype "passive"))
    )
    (net (code "126") (name "unconnected-(D9-AT0-Pad36)") (class "Default")
      (node (ref "D9") (pin "36") (pinfunction "AT0_36") (pintype "passive"))
    )
    (net (code "127") (name "unconnected-(D9-AT1-Pad37)") (class "Default")
      (node (ref "D9") (pin "37") (pinfunction "AT1_37") (pintype "passive"))
    )
    (net (code "128") (name "unconnected-(D9-PA0-Pad15)") (class "Default")
      (node (ref "D9") (pin "15") (pinfunction "PA0_15") (pintype "passive"))
    )
    (net (code "129") (name "unconnected-(D9-PA3-Pad18)") (class "Default")
      (node (ref "D9") (pin "18") (pinfunction "PA3_18") (pintype "passive"))
    )
    (net (code "130") (name "unconnected-(D9-PA4-Pad19)") (class "Default")
      (node (ref "D9") (pin "19") (pinfunction "PA4_19") (pintype "passive"))
    )
    (net (code "131") (name "unconnected-(D9-PA5-Pad20)") (class "Default")
      (node (ref "D9") (pin "20") (pinfunction "PA5_20") (pintype "passive"))
    )
    (net (code "132") (name "unconnected-(D9-PA6-Pad21)") (class "Default")
      (node (ref "D9") (pin "21") (pinfunction "PA6_21") (pintype "passive"))
    )
    (net (code "133") (name "unconnected-(D9-PA7-Pad22)") (class "Default")
      (node (ref "D9") (pin "22") (pinfunction "PA7_22") (pintype "passive"))
    )
    (net (code "134") (name "unconnected-(D9-PB5-Pad65)") (class "Default")
      (node (ref "D9") (pin "65") (pinfunction "PB5_65") (pintype "passive"))
    )
    (net (code "135") (name "unconnected-(D9-PB10-Pad28)") (class "Default")
      (node (ref "D9") (pin "28") (pinfunction "PB10_28") (pintype "passive"))
    )
    (net (code "136") (name "unconnected-(D9-PB11-Pad29)") (class "Default")
      (node (ref "D9") (pin "29") (pinfunction "PB11_29") (pintype "passive"))
    )
    (net (code "137") (name "unconnected-(D9-PB12-Pad46)") (class "Default")
      (node (ref "D9") (pin "46") (pinfunction "PB12_46") (pintype "passive"))
    )
    (net (code "138") (name "unconnected-(D9-PB13-Pad47)") (class "Default")
      (node (ref "D9") (pin "47") (pinfunction "PB13_47") (pintype "passive"))
    )
    (net (code "139") (name "unconnected-(D9-PB14-Pad48)") (class "Default")
      (node (ref "D9") (pin "48") (pinfunction "PB14_48") (pintype "passive"))
    )
    (net (code "140") (name "unconnected-(D9-PB15-Pad49)") (class "Default")
      (node (ref "D9") (pin "49") (pinfunction "PB15_49") (pintype "passive"))
    )
    (net (code "141") (name "unconnected-(D9-PC0-Pad9)") (class "Default")
      (node (ref "D9") (pin "9") (pinfunction "PC0_9") (pintype "passive"))
    )
    (net (code "142") (name "unconnected-(D9-PC1-Pad10)") (class "Default")
      (node (ref "D9") (pin "10") (pinfunction "PC1_10") (pintype "passive"))
    )
    (net (code "143") (name "unconnected-(D9-PC2-Pad11)") (class "Default")
      (node (ref "D9") (pin "11") (pinfunction "PC2_11") (pintype "passive"))
    )
    (net (code "144") (name "unconnected-(D9-PC3-Pad12)") (class "Default")
      (node (ref "D9") (pin "12") (pinfunction "PC3_12") (pintype "passive"))
    )
    (net (code "145") (name "unconnected-(D9-PC4-Pad25)") (class "Default")
      (node (ref "D9") (pin "25") (pinfunction "PC4_25") (pintype "passive"))
    )
    (net (code "146") (name "unconnected-(D9-PC5-Pad26)") (class "Default")
      (node (ref "D9") (pin "26") (pinfunction "PC5_26") (pintype "passive"))
    )
    (net (code "147") (name "unconnected-(D9-PC6-Pad50)") (class "Default")
      (node (ref "D9") (pin "50") (pinfunction "PC6_50") (pintype "passive"))
    )
    (net (code "148") (name "unconnected-(D9-PC10-Pad58)") (class "Default")
      (node (ref "D9") (pin "58") (pinfunction "PC10_58") (pintype "passive"))
    )
    (net (code "149") (name "unconnected-(D9-PC11-Pad59)") (class "Default")
      (node (ref "D9") (pin "59") (pinfunction "PC11_59") (pintype "passive"))
    )
    (net (code "150") (name "unconnected-(D9-PC12-Pad60)") (class "Default")
      (node (ref "D9") (pin "60") (pinfunction "PC12_60") (pintype "passive"))
    )
    (net (code "151") (name "unconnected-(D9-PC13-Pad2)") (class "Default")
      (node (ref "D9") (pin "2") (pinfunction "PC13_2") (pintype "passive"))
    )
    (net (code "152") (name "unconnected-(D9-PD0-Pad61)") (class "Default")
      (node (ref "D9") (pin "61") (pinfunction "PD0_61") (pintype "passive"))
    )
    (net (code "153") (name "unconnected-(D9-PD1-Pad62)") (class "Default")
      (node (ref "D9") (pin "62") (pinfunction "PD1_62") (pintype "passive"))
    )
    (net (code "154") (name "unconnected-(D9-PE4-Pad40)") (class "Default")
      (node (ref "D9") (pin "40") (pinfunction "PE4_40") (pintype "passive"))
    )
    (net (code "155") (name "unconnected-(WA1-NC-Pad5)") (class "Default")
      (node (ref "WA1") (pin "5") (pinfunction "NC_5") (pintype "passive"))
    )
    (net (code "156") (name "unconnected-(WA1-NC-Pad6)") (class "Default")
      (node (ref "WA1") (pin "6") (pinfunction "NC_6") (pintype "passive"))
    )
    (net (code "157") (name "unconnected-(WA1-NC-Pad7)") (class "Default")
      (node (ref "WA1") (pin "7") (pinfunction "NC_7") (pintype "passive"))
    )
    (net (code "158") (name "unconnected-(WA1-SC1-Pad1)") (class "Default")
      (node (ref "WA1") (pin "1") (pinfunction "SC1_1") (pintype "passive"))
    )
    (net (code "159") (name "unconnected-(WA1-SC2-Pad2)") (class "Default")
      (node (ref "WA1") (pin "2") (pinfunction "SC2_2") (pintype "passive"))
    )
  )
)
